# SCH-7-ESC5.net
KiCad netlist of a schematic drawn in Altium Designer
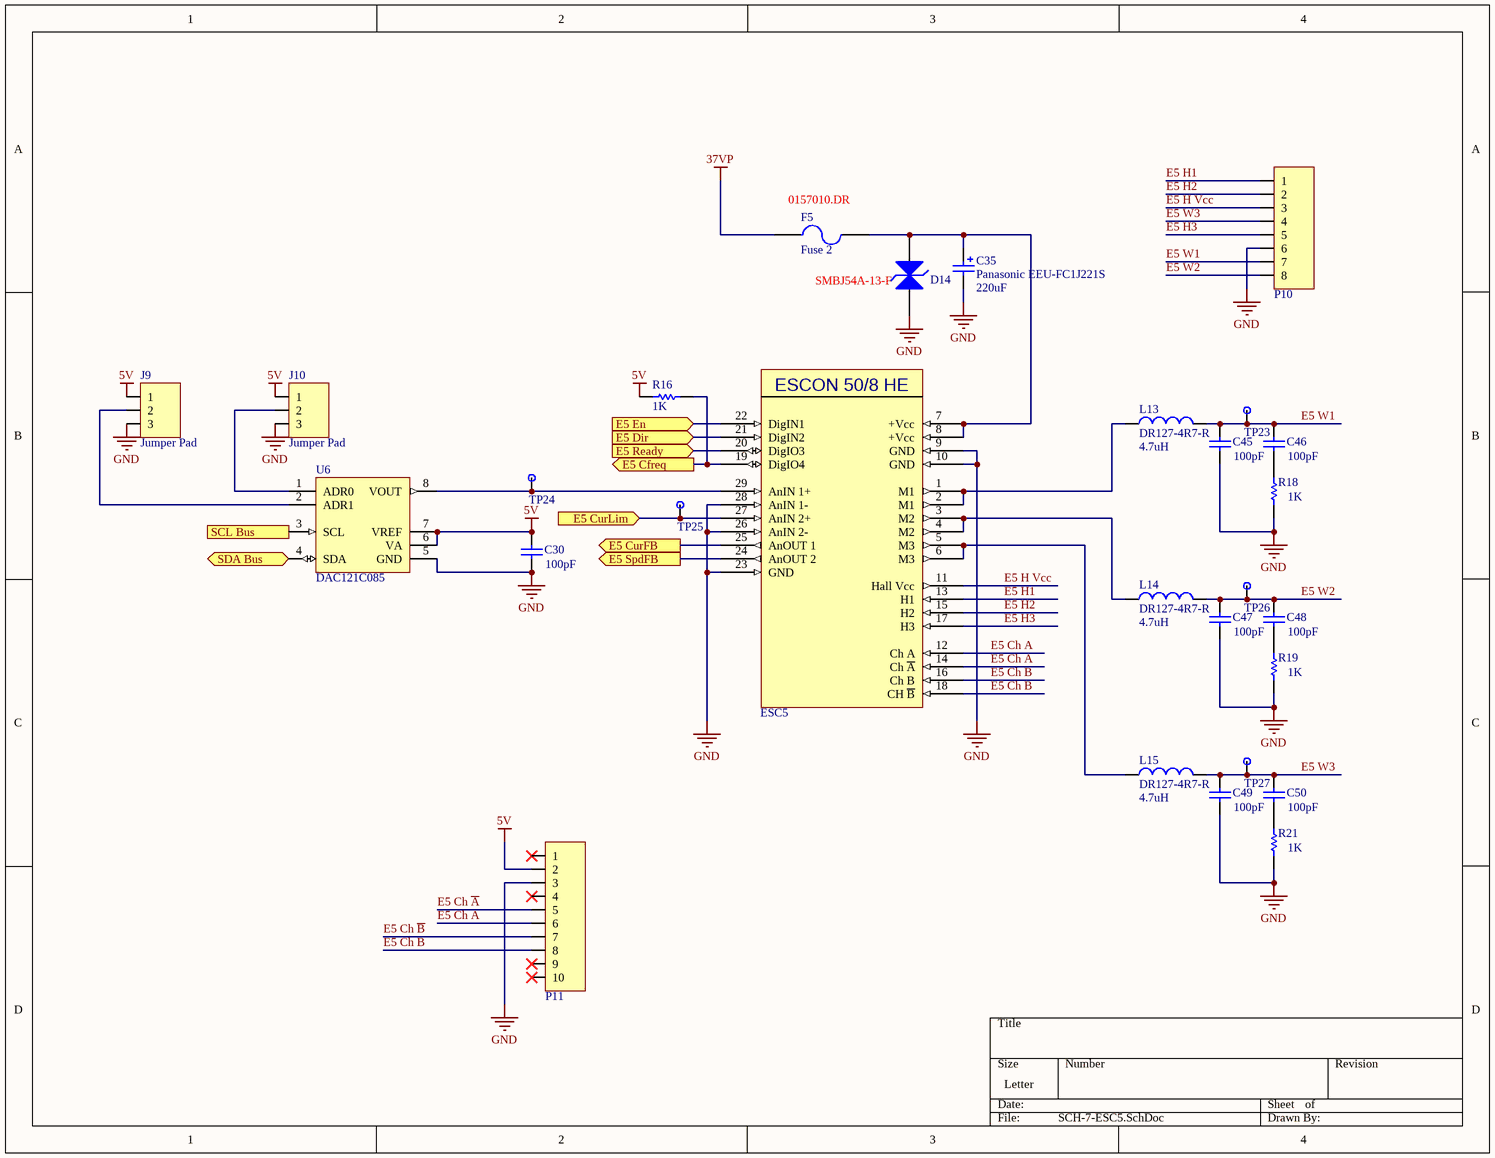
[diagram p0: SCH-7-ESC5.SchDoc]

(export (version "E")
  (design (tool "Eeschema 10.0.6"))
  (components
    (comp (ref "C30")
      (value "100pF")
      (footprint "C1206")
      (description "Capacitor (Semiconductor SIM Model)")
      (fields (field (name "Comment") "Cap Semi") (field (name "PUBLISHER") "Altium Limited"))
      (libsource (lib "Miscellaneous Devices") (part "Cap Semi"))
    )
    (comp (ref "C35")
      (value "Panasonic EEU-FC1J221S")
      (footprint "Panasonic EEU-FC1J221S")
      (description "Polarized Capacitor (Radial)")
      (fields (field (name "ALTIUM_VALUE") "220uF"))
      (libsource (lib "RSX_Capacitors") (part "Panasonic EEU-FC1J221S"))
    )
    (comp (ref "C45")
      (value "100pF")
      (footprint "C1206")
      (description "Capacitor (Semiconductor SIM Model)")
      (fields (field (name "Comment") "Cap Semi") (field (name "PUBLISHER") "Altium Limited"))
      (libsource (lib "Miscellaneous Devices") (part "Cap Semi"))
    )
    (comp (ref "C46")
      (value "100pF")
      (footprint "C1206")
      (description "Capacitor (Semiconductor SIM Model)")
      (fields (field (name "Comment") "Cap Semi") (field (name "PUBLISHER") "Altium Limited"))
      (libsource (lib "Miscellaneous Devices") (part "Cap Semi"))
    )
    (comp (ref "C47")
      (value "100pF")
      (footprint "C1206")
      (description "Capacitor (Semiconductor SIM Model)")
      (fields (field (name "Comment") "Cap Semi") (field (name "PUBLISHER") "Altium Limited"))
      (libsource (lib "Miscellaneous Devices") (part "Cap Semi"))
    )
    (comp (ref "C48")
      (value "100pF")
      (footprint "C1206")
      (description "Capacitor (Semiconductor SIM Model)")
      (fields (field (name "Comment") "Cap Semi") (field (name "PUBLISHER") "Altium Limited"))
      (libsource (lib "Miscellaneous Devices") (part "Cap Semi"))
    )
    (comp (ref "C49")
      (value "100pF")
      (footprint "C1206")
      (description "Capacitor (Semiconductor SIM Model)")
      (fields (field (name "Comment") "Cap Semi") (field (name "PUBLISHER") "Altium Limited"))
      (libsource (lib "Miscellaneous Devices") (part "Cap Semi"))
    )
    (comp (ref "C50")
      (value "100pF")
      (footprint "C1206")
      (description "Capacitor (Semiconductor SIM Model)")
      (fields (field (name "Comment") "Cap Semi") (field (name "PUBLISHER") "Altium Limited"))
      (libsource (lib "Miscellaneous Devices") (part "Cap Semi"))
    )
    (comp (ref "D14")
      (value "TVS_DIODE")
      (footprint "SMBJ54A-13-F")
      (description "TVS Diode")
      (fields (field (name "PUBLISHER") "Altium Limited"))
      (libsource (lib "RSX_Diodes") (part "TVS_DIODE"))
    )
    (comp (ref "ESC5")
      (value "ESCON 50/8 HE")
      (footprint "ESCON 50/8 HE")
      (description "ESCON Module 50/8 HE Servocontroller")
      (libsource (lib "RSX_Modules") (part "ESCON 50/8 HE"))
    )
    (comp (ref "F5")
      (value "Fuse 2")
      (footprint "0157010.DR")
      (description "Fuse")
      (fields (field (name "PUBLISHER") "Altium Limited"))
      (libsource (lib "RSX_Miscellaneous") (part "Fuse 2"))
    )
    (comp (ref "J9")
      (value "Jumper Pad")
      (footprint "3 Pad TH")
      (libsource (lib "RSX_Test_Points") (part "3 Pad Jump Sel"))
    )
    (comp (ref "J10")
      (value "Jumper Pad")
      (footprint "3 Pad TH")
      (libsource (lib "RSX_Test_Points") (part "3 Pad Jump Sel"))
    )
    (comp (ref "L13")
      (value "DR127-4R7-R")
      (footprint "DR127-4R7-R")
      (description "4.7µH Shielded Wirewound Inductor 8.25A 9.17mOhm Nonstandard")
      (fields (field (name "ALTIUM_VALUE") "4.7uH") (field (name "PUBLISHER") "Altium Limited"))
      (libsource (lib "RSX_Inductors") (part "DR127-4R7-R"))
    )
    (comp (ref "L14")
      (value "DR127-4R7-R")
      (footprint "DR127-4R7-R")
      (description "4.7µH Shielded Wirewound Inductor 8.25A 9.17mOhm Nonstandard")
      (fields (field (name "ALTIUM_VALUE") "4.7uH") (field (name "PUBLISHER") "Altium Limited"))
      (libsource (lib "RSX_Inductors") (part "DR127-4R7-R"))
    )
    (comp (ref "L15")
      (value "DR127-4R7-R")
      (footprint "DR127-4R7-R")
      (description "4.7µH Shielded Wirewound Inductor 8.25A 9.17mOhm Nonstandard")
      (fields (field (name "ALTIUM_VALUE") "4.7uH") (field (name "PUBLISHER") "Altium Limited"))
      (libsource (lib "RSX_Inductors") (part "DR127-4R7-R"))
    )
    (comp (ref "P10")
      (value "Mini-Fit Jr 8 Pos")
      (footprint "Molex Mini-Fit Jr 0039281083")
      (libsource (lib "RSX_Connectors") (part "Molex Mini-Fit Jr 8pos Vert"))
    )
    (comp (ref "P11")
      (value "Header_10_Pos_Ribbon Male")
      (footprint "3M_2510-6002UB")
      (description "3M_2510-6002UB")
      (libsource (lib "RSX_Connectors") (part "Header_10_Pos_Ribbon Male"))
    )
    (comp (ref "R16")
      (value "1K")
      (footprint "RESC1608X06N_0603")
      (description "Resistor")
      (fields (field (name "Comment") "Res1") (field (name "PUBLISHER") "Altium Limited"))
      (libsource (lib "RSX_Resistors") (part "Res1"))
    )
    (comp (ref "R18")
      (value "1K")
      (footprint "RESC1608X06N_0603")
      (description "Resistor")
      (fields (field (name "Comment") "Res1") (field (name "PUBLISHER") "Altium Limited"))
      (libsource (lib "RSX_Resistors") (part "Res1"))
    )
    (comp (ref "R19")
      (value "1K")
      (footprint "RESC1608X06N_0603")
      (description "Resistor")
      (fields (field (name "Comment") "Res1") (field (name "PUBLISHER") "Altium Limited"))
      (libsource (lib "RSX_Resistors") (part "Res1"))
    )
    (comp (ref "R21")
      (value "1K")
      (footprint "RESC1608X06N_0603")
      (description "Resistor")
      (fields (field (name "Comment") "Res1") (field (name "PUBLISHER") "Altium Limited"))
      (libsource (lib "RSX_Resistors") (part "Res1"))
    )
    (comp (ref "TP23")
      (value "TestPt")
      (footprint "50_MIL_PAD")
      (libsource (lib "RSX_Test_Points") (part "TestPt"))
    )
    (comp (ref "TP24")
      (value "TestPt")
      (footprint "50_MIL_PAD")
      (libsource (lib "RSX_Test_Points") (part "TestPt"))
    )
    (comp (ref "TP25")
      (value "TestPt")
      (footprint "50_MIL_PAD")
      (libsource (lib "RSX_Test_Points") (part "TestPt"))
    )
    (comp (ref "TP26")
      (value "TestPt")
      (footprint "50_MIL_PAD")
      (libsource (lib "RSX_Test_Points") (part "TestPt"))
    )
    (comp (ref "TP27")
      (value "TestPt")
      (footprint "50_MIL_PAD")
      (libsource (lib "RSX_Test_Points") (part "TestPt"))
    )
    (comp (ref "U6")
      (value "DAC121C085")
      (footprint "MUA08A_L")
      (fields (field (name "MANUFACTURER") "National Semiconductor"))
      (libsource (lib "RSX_Schematics") (part "DAC121C085"))
    )
  )
  (nets
    (net (code "1") (name "/E5 Cfreq") (class "Default")
      (node (ref "ESC5") (pin "19") (pinfunction "DigIO4_19") (pintype "bidirectional"))
      (node (ref "R16") (pin "1") (pinfunction "1_1") (pintype "passive"))
    )
    (net (code "2") (name "/E5 Ch A") (class "Default")
      (node (ref "ESC5") (pin "12") (pinfunction "Ch_A_12") (pintype "input"))
      (node (ref "P11") (pin "6") (pinfunction "6_6") (pintype "passive"))
    )
    (net (code "3") (name "/E5 Ch B") (class "Default")
      (node (ref "ESC5") (pin "16") (pinfunction "Ch_B_16") (pintype "input"))
      (node (ref "P11") (pin "8") (pinfunction "8_8") (pintype "passive"))
    )
    (net (code "4") (name "/E5 Ch ~{A}") (class "Default")
      (node (ref "ESC5") (pin "14") (pinfunction "Ch_~{A}_14") (pintype "input"))
      (node (ref "P11") (pin "5") (pinfunction "5_5") (pintype "passive"))
    )
    (net (code "5") (name "/E5 Ch ~{B}") (class "Default")
      (node (ref "ESC5") (pin "18") (pinfunction "CH_~{B}_18") (pintype "input"))
      (node (ref "P11") (pin "7") (pinfunction "7_7") (pintype "passive"))
    )
    (net (code "6") (name "/E5 CurFB") (class "Default")
      (node (ref "ESC5") (pin "25") (pinfunction "AnOUT_1_25") (pintype "output"))
    )
    (net (code "7") (name "/E5 CurLim") (class "Default")
      (node (ref "ESC5") (pin "27") (pinfunction "AnIN_2+_27") (pintype "input"))
      (node (ref "TP25") (pin "1") (pinfunction "1_1") (pintype "passive"))
    )
    (net (code "8") (name "/E5 Dir") (class "Default")
      (node (ref "ESC5") (pin "21") (pinfunction "DigIN2_21") (pintype "input"))
    )
    (net (code "9") (name "/E5 En") (class "Default")
      (node (ref "ESC5") (pin "22") (pinfunction "DigIN1_22") (pintype "input"))
    )
    (net (code "10") (name "/E5 H Vcc") (class "Default")
      (node (ref "ESC5") (pin "11") (pinfunction "Hall_Vcc_11") (pintype "output"))
      (node (ref "P10") (pin "3") (pinfunction "3_3") (pintype "passive"))
    )
    (net (code "11") (name "/E5 H1") (class "Default")
      (node (ref "ESC5") (pin "13") (pinfunction "H1_13") (pintype "input"))
      (node (ref "P10") (pin "1") (pinfunction "1_1") (pintype "passive"))
    )
    (net (code "12") (name "/E5 H2") (class "Default")
      (node (ref "ESC5") (pin "15") (pinfunction "H2_15") (pintype "input"))
      (node (ref "P10") (pin "2") (pinfunction "2_2") (pintype "passive"))
    )
    (net (code "13") (name "/E5 H3") (class "Default")
      (node (ref "ESC5") (pin "17") (pinfunction "H3_17") (pintype "input"))
      (node (ref "P10") (pin "5") (pinfunction "5_5") (pintype "passive"))
    )
    (net (code "14") (name "/E5 Ready") (class "Default")
      (node (ref "ESC5") (pin "20") (pinfunction "DigIO3_20") (pintype "bidirectional"))
    )
    (net (code "15") (name "/E5 SpdFB") (class "Default")
      (node (ref "ESC5") (pin "24") (pinfunction "AnOUT_2_24") (pintype "output"))
    )
    (net (code "16") (name "/E5 W1") (class "Default")
      (node (ref "C45") (pin "2") (pinfunction "2_2") (pintype "passive"))
      (node (ref "C46") (pin "2") (pinfunction "2_2") (pintype "passive"))
      (node (ref "L13") (pin "2") (pinfunction "2_2") (pintype "passive"))
      (node (ref "P10") (pin "7") (pinfunction "7_7") (pintype "passive"))
      (node (ref "TP23") (pin "1") (pinfunction "1_1") (pintype "passive"))
    )
    (net (code "17") (name "/E5 W2") (class "Default")
      (node (ref "C47") (pin "2") (pinfunction "2_2") (pintype "passive"))
      (node (ref "C48") (pin "2") (pinfunction "2_2") (pintype "passive"))
      (node (ref "L14") (pin "2") (pinfunction "2_2") (pintype "passive"))
      (node (ref "P10") (pin "8") (pinfunction "8_8") (pintype "passive"))
      (node (ref "TP26") (pin "1") (pinfunction "1_1") (pintype "passive"))
    )
    (net (code "18") (name "/E5 W3") (class "Default")
      (node (ref "C49") (pin "2") (pinfunction "2_2") (pintype "passive"))
      (node (ref "C50") (pin "2") (pinfunction "2_2") (pintype "passive"))
      (node (ref "L15") (pin "2") (pinfunction "2_2") (pintype "passive"))
      (node (ref "P10") (pin "4") (pinfunction "4_4") (pintype "passive"))
      (node (ref "TP27") (pin "1") (pinfunction "1_1") (pintype "passive"))
    )
    (net (code "19") (name "/SCL Bus") (class "Default")
      (node (ref "U6") (pin "3") (pinfunction "SCL_3") (pintype "input"))
    )
    (net (code "20") (name "/SDA Bus") (class "Default")
      (node (ref "U6") (pin "4") (pinfunction "SDA_4") (pintype "bidirectional"))
    )
    (net (code "21") (name "5V") (class "Default")
      (node (ref "C30") (pin "2") (pinfunction "2_2") (pintype "passive"))
      (node (ref "J10") (pin "1") (pinfunction "1_1") (pintype "passive"))
      (node (ref "J9") (pin "1") (pinfunction "1_1") (pintype "passive"))
      (node (ref "P11") (pin "2") (pinfunction "2_2") (pintype "passive"))
      (node (ref "R16") (pin "2") (pinfunction "2_2") (pintype "passive"))
      (node (ref "U6") (pin "6") (pinfunction "VA_6") (pintype "power_in"))
      (node (ref "U6") (pin "7") (pinfunction "VREF_7") (pintype "power_in"))
    )
    (net (code "22") (name "37VP") (class "Default")
      (node (ref "F5") (pin "1") (pinfunction "1_1") (pintype "passive"))
    )
    (net (code "23") (name "GND") (class "Default")
      (node (ref "C30") (pin "1") (pinfunction "1_1") (pintype "passive"))
      (node (ref "C35") (pin "2") (pinfunction "2_2") (pintype "passive"))
      (node (ref "C45") (pin "1") (pinfunction "1_1") (pintype "passive"))
      (node (ref "C47") (pin "1") (pinfunction "1_1") (pintype "passive"))
      (node (ref "C49") (pin "1") (pinfunction "1_1") (pintype "passive"))
      (node (ref "D14") (pin "1") (pinfunction "A_1") (pintype "passive"))
      (node (ref "ESC5") (pin "10") (pinfunction "GND_10") (pintype "input"))
      (node (ref "ESC5") (pin "23") (pinfunction "GND_23") (pintype "input"))
      (node (ref "ESC5") (pin "26") (pinfunction "AnIN_2-_26") (pintype "input"))
      (node (ref "ESC5") (pin "28") (pinfunction "AnIN_1-_28") (pintype "input"))
      (node (ref "ESC5") (pin "9") (pinfunction "GND_9") (pintype "input"))
      (node (ref "J10") (pin "3") (pinfunction "3_3") (pintype "passive"))
      (node (ref "J9") (pin "3") (pinfunction "3_3") (pintype "passive"))
      (node (ref "P10") (pin "6") (pinfunction "6_6") (pintype "passive"))
      (node (ref "P11") (pin "3") (pinfunction "3_3") (pintype "passive"))
      (node (ref "R18") (pin "1") (pinfunction "1_1") (pintype "passive"))
      (node (ref "R19") (pin "1") (pinfunction "1_1") (pintype "passive"))
      (node (ref "R21") (pin "1") (pinfunction "1_1") (pintype "passive"))
      (node (ref "U6") (pin "5") (pinfunction "GND_5") (pintype "power_in"))
    )
    (net (code "24") (name "Net-(C46-Pad1)") (class "Default")
      (node (ref "C46") (pin "1") (pinfunction "1_1") (pintype "passive"))
      (node (ref "R18") (pin "2") (pinfunction "2_2") (pintype "passive"))
    )
    (net (code "25") (name "Net-(C48-Pad1)") (class "Default")
      (node (ref "C48") (pin "1") (pinfunction "1_1") (pintype "passive"))
      (node (ref "R19") (pin "2") (pinfunction "2_2") (pintype "passive"))
    )
    (net (code "26") (name "Net-(C50-Pad1)") (class "Default")
      (node (ref "C50") (pin "1") (pinfunction "1_1") (pintype "passive"))
      (node (ref "R21") (pin "2") (pinfunction "2_2") (pintype "passive"))
    )
    (net (code "27") (name "Net-(D14-K)") (class "Default")
      (node (ref "C35") (pin "1") (pinfunction "1_1") (pintype "passive"))
      (node (ref "D14") (pin "2") (pinfunction "K_2") (pintype "passive"))
      (node (ref "ESC5") (pin "7") (pinfunction "+Vcc_7") (pintype "input"))
      (node (ref "ESC5") (pin "8") (pinfunction "+Vcc_8") (pintype "input"))
      (node (ref "F5") (pin "2") (pinfunction "2_2") (pintype "passive"))
    )
    (net (code "28") (name "Net-(ESC5-AnIN_1+)") (class "Default")
      (node (ref "ESC5") (pin "29") (pinfunction "AnIN_1+_29") (pintype "input"))
      (node (ref "TP24") (pin "1") (pinfunction "1_1") (pintype "passive"))
      (node (ref "U6") (pin "8") (pinfunction "VOUT_8") (pintype "output"))
    )
    (net (code "29") (name "Net-(ESC5-M1-Pad1)") (class "Default")
      (node (ref "ESC5") (pin "1") (pinfunction "M1_1") (pintype "output"))
      (node (ref "ESC5") (pin "2") (pinfunction "M1_2") (pintype "output"))
      (node (ref "L13") (pin "1") (pinfunction "1_1") (pintype "passive"))
    )
    (net (code "30") (name "Net-(ESC5-M2-Pad3)") (class "Default")
      (node (ref "ESC5") (pin "3") (pinfunction "M2_3") (pintype "output"))
      (node (ref "ESC5") (pin "4") (pinfunction "M2_4") (pintype "output"))
      (node (ref "L14") (pin "1") (pinfunction "1_1") (pintype "passive"))
    )
    (net (code "31") (name "Net-(ESC5-M3-Pad5)") (class "Default")
      (node (ref "ESC5") (pin "5") (pinfunction "M3_5") (pintype "output"))
      (node (ref "ESC5") (pin "6") (pinfunction "M3_6") (pintype "output"))
      (node (ref "L15") (pin "1") (pinfunction "1_1") (pintype "passive"))
    )
    (net (code "32") (name "Net-(U6-ADR0)") (class "Default")
      (node (ref "J10") (pin "2") (pinfunction "2_2") (pintype "passive"))
      (node (ref "U6") (pin "1") (pinfunction "ADR0_1") (pintype "tri_state"))
    )
    (net (code "33") (name "Net-(U6-ADR1)") (class "Default")
      (node (ref "J9") (pin "2") (pinfunction "2_2") (pintype "passive"))
      (node (ref "U6") (pin "2") (pinfunction "ADR1_2") (pintype "tri_state"))
    )
    (net (code "34") (name "unconnected-(P11-Pad1)") (class "Default")
      (node (ref "P11") (pin "1") (pinfunction "1_1") (pintype "passive+no_connect"))
    )
    (net (code "35") (name "unconnected-(P11-Pad4)") (class "Default")
      (node (ref "P11") (pin "4") (pinfunction "4_4") (pintype "passive+no_connect"))
    )
    (net (code "36") (name "unconnected-(P11-Pad9)") (class "Default")
      (node (ref "P11") (pin "9") (pinfunction "9_9") (pintype "passive+no_connect"))
    )
    (net (code "37") (name "unconnected-(P11-Pad10)") (class "Default")
      (node (ref "P11") (pin "10") (pinfunction "10_10") (pintype "passive+no_connect"))
    )
  )
)
